# LevelShifter.net
KiCad netlist of a schematic drawn in EAGLE
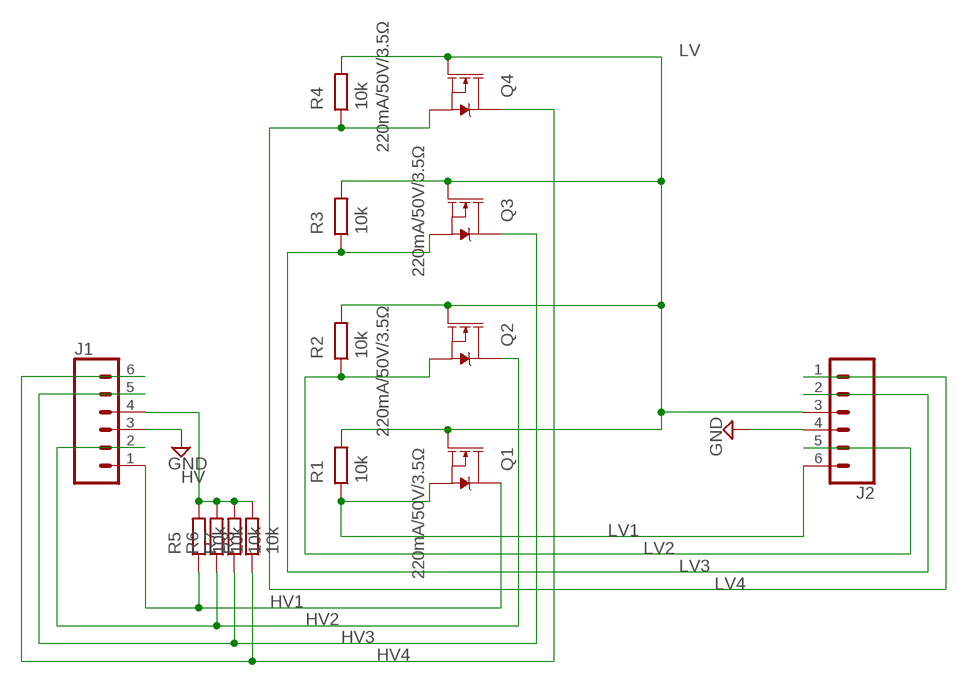
[diagram p0: schematic, sheet 1]

(export (version "E")
  (design (tool "Eeschema 10.0.6"))
  (components
    (comp (ref "J1")
      (value "CONN_06NO_SILK_NO_POP")
      (footprint "eagle-import:1X06_NO_SILK")
      (libsource (lib "eagle-import") (part "CONN_06NO_SILK_NO_POP"))
    )
    (comp (ref "J2")
      (value "CONN_06NO_SILK_NO_POP")
      (footprint "eagle-import:1X06_NO_SILK")
      (libsource (lib "eagle-import") (part "CONN_06NO_SILK_NO_POP"))
    )
    (comp (ref "Q1")
      (value "220mA/50V/3.5Ω")
      (footprint "eagle-import:SOT23-3")
      (libsource (lib "eagle-import") (part "MOSFET-NCH-BSS138"))
    )
    (comp (ref "Q2")
      (value "220mA/50V/3.5Ω")
      (footprint "eagle-import:SOT23-3")
      (libsource (lib "eagle-import") (part "MOSFET-NCH-BSS138"))
    )
    (comp (ref "Q3")
      (value "220mA/50V/3.5Ω")
      (footprint "eagle-import:SOT23-3")
      (libsource (lib "eagle-import") (part "MOSFET-NCH-BSS138"))
    )
    (comp (ref "Q4")
      (value "220mA/50V/3.5Ω")
      (footprint "eagle-import:SOT23-3")
      (libsource (lib "eagle-import") (part "MOSFET-NCH-BSS138"))
    )
    (comp (ref "R1")
      (value "10k")
      (footprint "eagle-import:RESC1608X60")
      (libsource (lib "eagle-import") (part "RCHIP-0603(1608-METRIC)_"))
    )
    (comp (ref "R2")
      (value "10k")
      (footprint "eagle-import:RESC1608X60")
      (libsource (lib "eagle-import") (part "RCHIP-0603(1608-METRIC)_"))
    )
    (comp (ref "R3")
      (value "10k")
      (footprint "eagle-import:RESC1608X60")
      (libsource (lib "eagle-import") (part "RCHIP-0603(1608-METRIC)_"))
    )
    (comp (ref "R4")
      (value "10k")
      (footprint "eagle-import:RESC1608X60")
      (libsource (lib "eagle-import") (part "RCHIP-0603(1608-METRIC)_"))
    )
    (comp (ref "R5")
      (value "10k")
      (footprint "eagle-import:RESC1608X60")
      (libsource (lib "eagle-import") (part "RCHIP-0603(1608-METRIC)_"))
    )
    (comp (ref "R6")
      (value "10k")
      (footprint "eagle-import:RESC1608X60")
      (libsource (lib "eagle-import") (part "RCHIP-0603(1608-METRIC)_"))
    )
    (comp (ref "R7")
      (value "10k")
      (footprint "eagle-import:RESC1608X60")
      (libsource (lib "eagle-import") (part "RCHIP-0603(1608-METRIC)_"))
    )
    (comp (ref "R8")
      (value "10k")
      (footprint "eagle-import:RESC1608X60")
      (libsource (lib "eagle-import") (part "RCHIP-0603(1608-METRIC)_"))
    )
  )
  (nets
    (net (code "1") (name "/HV") (class "Default")
      (node (ref "J1") (pin "4") (pinfunction "4_4") (pintype "passive"))
      (node (ref "R5") (pin "2") (pinfunction "2_2") (pintype "passive"))
      (node (ref "R6") (pin "2") (pinfunction "2_2") (pintype "passive"))
      (node (ref "R7") (pin "2") (pinfunction "2_2") (pintype "passive"))
      (node (ref "R8") (pin "2") (pinfunction "2_2") (pintype "passive"))
    )
    (net (code "2") (name "/HV1") (class "Default")
      (node (ref "J1") (pin "1") (pinfunction "1_1") (pintype "passive"))
      (node (ref "Q1") (pin "3") (pinfunction "D_3") (pintype "bidirectional"))
      (node (ref "R5") (pin "1") (pinfunction "1_1") (pintype "passive"))
    )
    (net (code "3") (name "/HV2") (class "Default")
      (node (ref "J1") (pin "2") (pinfunction "2_2") (pintype "passive"))
      (node (ref "Q2") (pin "3") (pinfunction "D_3") (pintype "bidirectional"))
      (node (ref "R6") (pin "1") (pinfunction "1_1") (pintype "passive"))
    )
    (net (code "4") (name "/HV3") (class "Default")
      (node (ref "J1") (pin "5") (pinfunction "5_5") (pintype "passive"))
      (node (ref "Q3") (pin "3") (pinfunction "D_3") (pintype "bidirectional"))
      (node (ref "R7") (pin "1") (pinfunction "1_1") (pintype "passive"))
    )
    (net (code "5") (name "/HV4") (class "Default")
      (node (ref "J1") (pin "6") (pinfunction "6_6") (pintype "passive"))
      (node (ref "Q4") (pin "3") (pinfunction "D_3") (pintype "bidirectional"))
      (node (ref "R8") (pin "1") (pinfunction "1_1") (pintype "passive"))
    )
    (net (code "6") (name "/LV") (class "Default")
      (node (ref "J2") (pin "3") (pinfunction "3_3") (pintype "passive"))
      (node (ref "Q1") (pin "1") (pinfunction "G_1") (pintype "bidirectional"))
      (node (ref "Q2") (pin "1") (pinfunction "G_1") (pintype "bidirectional"))
      (node (ref "Q3") (pin "1") (pinfunction "G_1") (pintype "bidirectional"))
      (node (ref "Q4") (pin "1") (pinfunction "G_1") (pintype "bidirectional"))
      (node (ref "R1") (pin "2") (pinfunction "2_2") (pintype "passive"))
      (node (ref "R2") (pin "2") (pinfunction "2_2") (pintype "passive"))
      (node (ref "R3") (pin "2") (pinfunction "2_2") (pintype "passive"))
      (node (ref "R4") (pin "2") (pinfunction "2_2") (pintype "passive"))
    )
    (net (code "7") (name "/LV1") (class "Default")
      (node (ref "J2") (pin "6") (pinfunction "6_6") (pintype "passive"))
      (node (ref "Q1") (pin "2") (pinfunction "S_2") (pintype "bidirectional"))
      (node (ref "R1") (pin "1") (pinfunction "1_1") (pintype "passive"))
    )
    (net (code "8") (name "/LV2") (class "Default")
      (node (ref "J2") (pin "5") (pinfunction "5_5") (pintype "passive"))
      (node (ref "Q2") (pin "2") (pinfunction "S_2") (pintype "bidirectional"))
      (node (ref "R2") (pin "1") (pinfunction "1_1") (pintype "passive"))
    )
    (net (code "9") (name "/LV3") (class "Default")
      (node (ref "J2") (pin "2") (pinfunction "2_2") (pintype "passive"))
      (node (ref "Q3") (pin "2") (pinfunction "S_2") (pintype "bidirectional"))
      (node (ref "R3") (pin "1") (pinfunction "1_1") (pintype "passive"))
    )
    (net (code "10") (name "/LV4") (class "Default")
      (node (ref "J2") (pin "1") (pinfunction "1_1") (pintype "passive"))
      (node (ref "Q4") (pin "2") (pinfunction "S_2") (pintype "bidirectional"))
      (node (ref "R4") (pin "1") (pinfunction "1_1") (pintype "passive"))
    )
    (net (code "11") (name "GND") (class "Default")
      (node (ref "J1") (pin "3") (pinfunction "3_3") (pintype "passive"))
      (node (ref "J2") (pin "4") (pinfunction "4_4") (pintype "passive"))
    )
  )
)
